# ADC-Z-DOK.net
KiCad netlist of a schematic drawn in Altium Designer
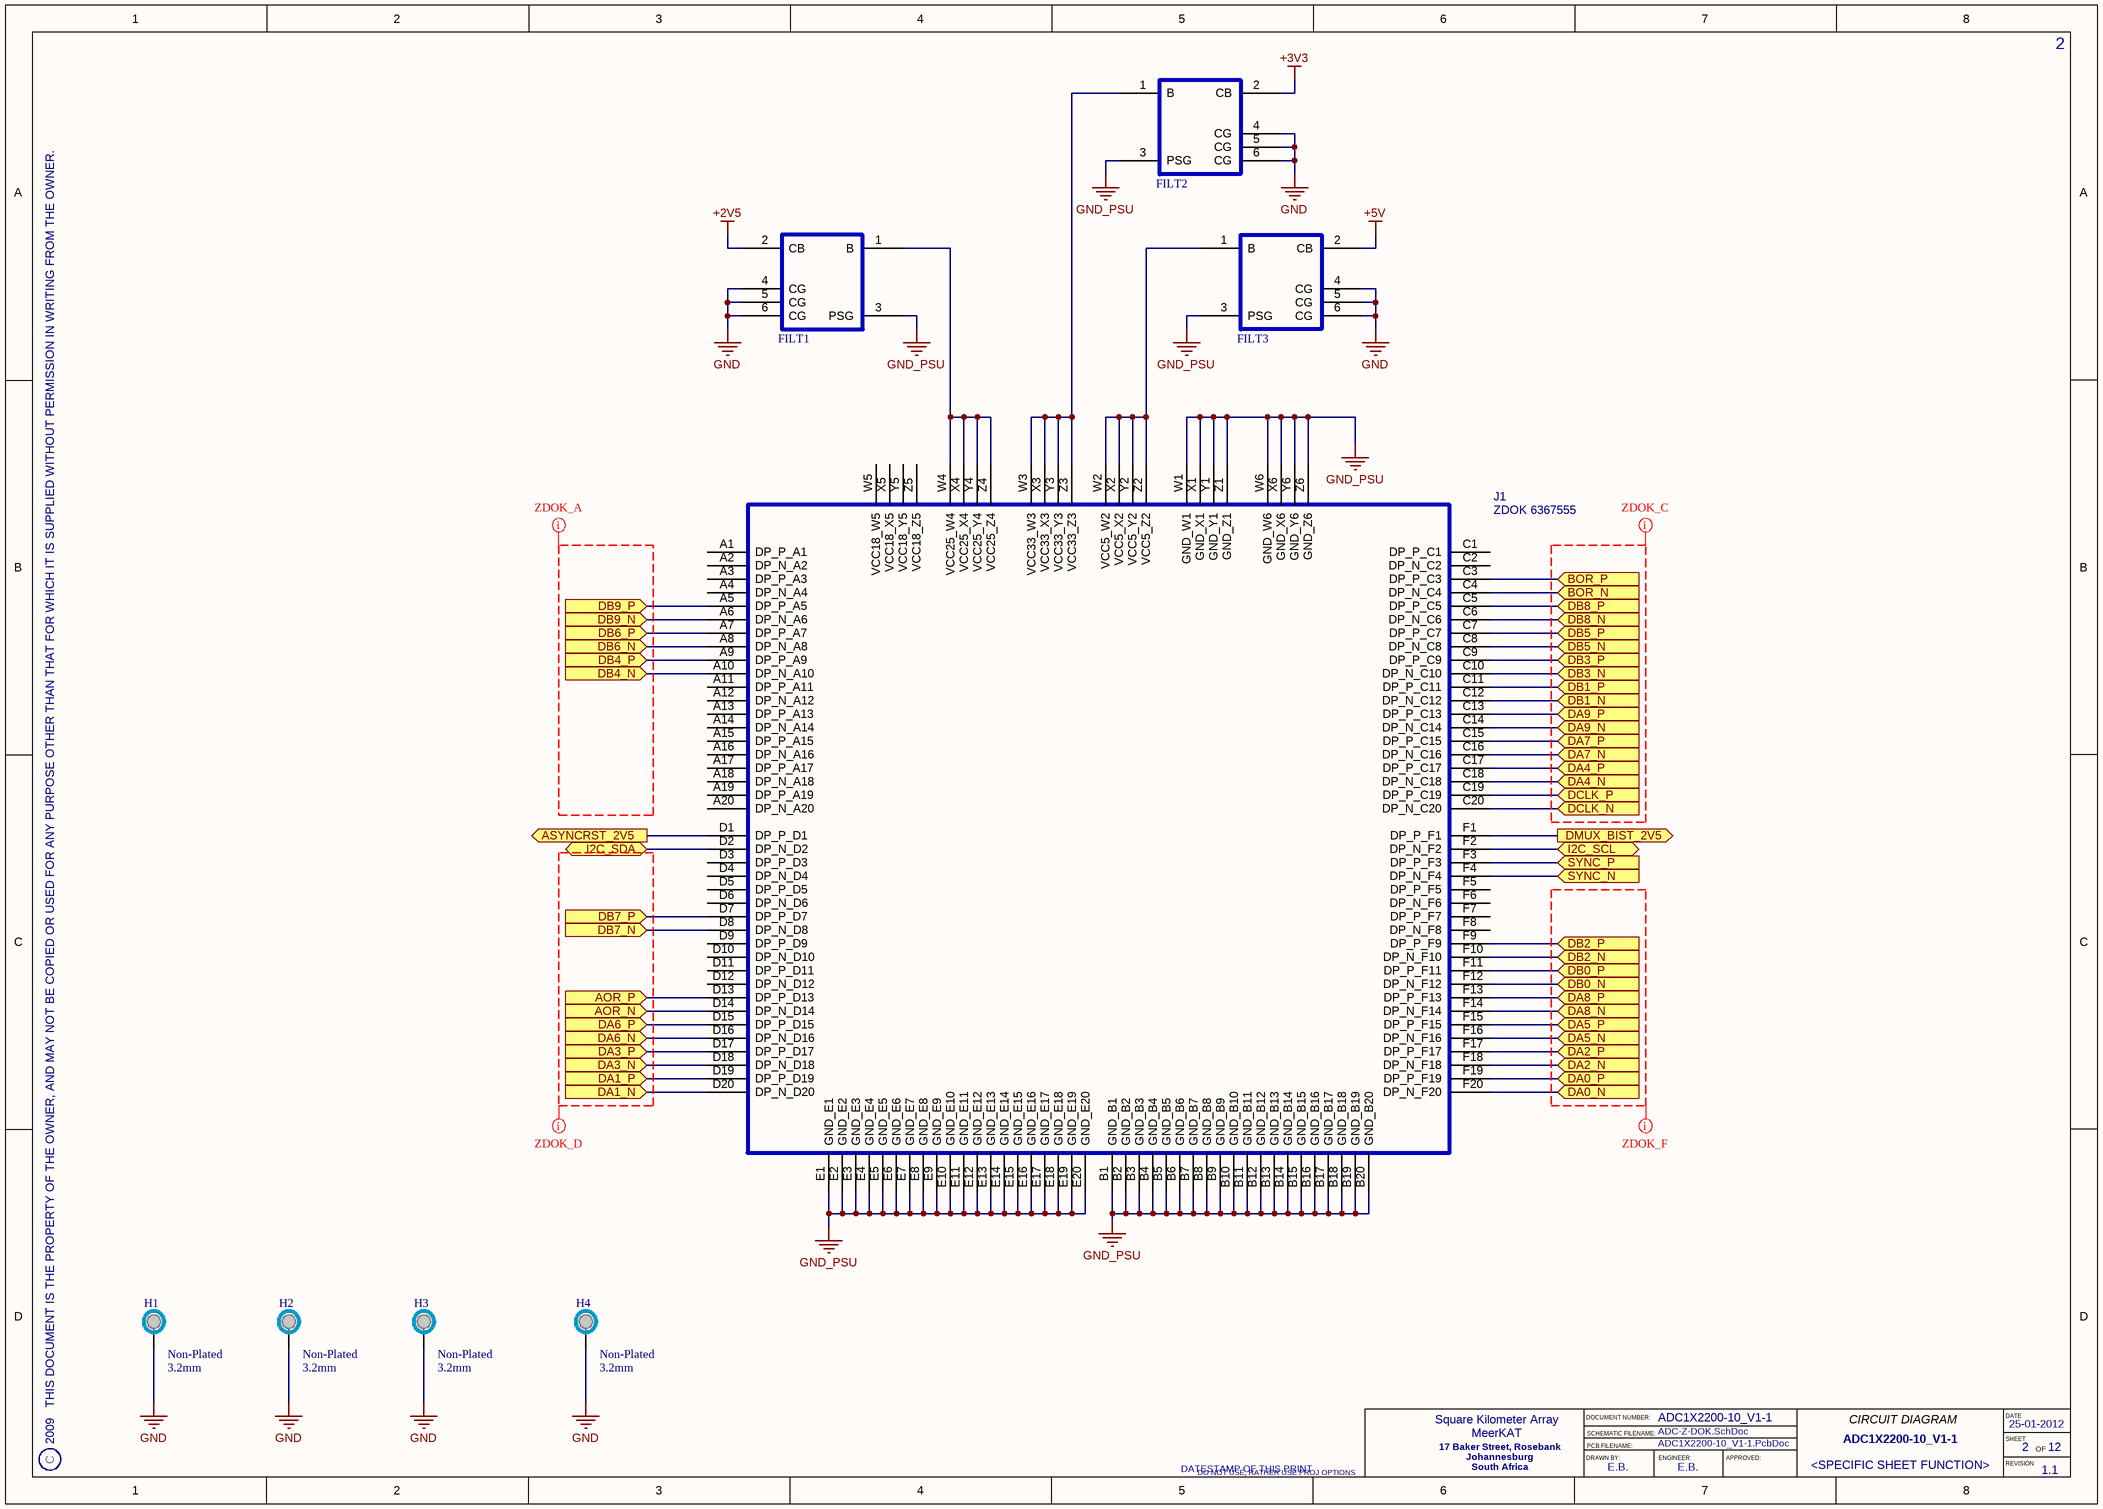
[diagram p0: ADC-Z-DOK.SchDoc]

(export (version "E")
  (design (tool "Eeschema 10.0.6"))
  (components
    (comp (ref "FILT1")
      (value "BNX002-01")
      (footprint "BNX002-01")
      (fields (field (name "CHECKED_BY") "*"))
      (libsource (lib "ADC1X2200-10_V1-0") (part "BNX002-01"))
    )
    (comp (ref "FILT2")
      (value "BNX002-01")
      (footprint "BNX002-01")
      (fields (field (name "CHECKED_BY") "*"))
      (libsource (lib "ADC1X2200-10_V1-0") (part "BNX002-01"))
    )
    (comp (ref "FILT3")
      (value "BNX002-01")
      (footprint "BNX002-01")
      (fields (field (name "CHECKED_BY") "*"))
      (libsource (lib "ADC1X2200-10_V1-0") (part "BNX002-01"))
    )
    (comp (ref "H1")
      (value "Non-Plated")
      (footprint "HOLE")
      (description "PCB Mounting Hole")
      (fields (field (name "HOLEDIA") "3.2mm"))
      (libsource (lib "Analog_Outputs") (part "Unplated Hole_3.2mm"))
    )
    (comp (ref "H2")
      (value "Non-Plated")
      (footprint "HOLE")
      (description "PCB Mounting Hole")
      (fields (field (name "HOLEDIA") "3.2mm"))
      (libsource (lib "Analog_Outputs") (part "Unplated Hole_3.2mm"))
    )
    (comp (ref "H3")
      (value "Non-Plated")
      (footprint "HOLE")
      (description "PCB Mounting Hole")
      (fields (field (name "HOLEDIA") "3.2mm"))
      (libsource (lib "Analog_Outputs") (part "Unplated Hole_3.2mm"))
    )
    (comp (ref "H4")
      (value "Non-Plated")
      (footprint "HOLE")
      (description "PCB Mounting Hole")
      (fields (field (name "HOLEDIA") "3.2mm"))
      (libsource (lib "Analog_Outputs") (part "Unplated Hole_3.2mm"))
    )
    (comp (ref "J1")
      (value "Z-DOK")
      (footprint "TYCO6367555")
      (fields
        (field (name "MANUFACTURER_PN") "ZDOK 6367555")
        (field (name "CREATED_BY") "CT")
        (field (name "CHECKED_BY") "*")
      )
      (libsource (lib "Charles-TEMP") (part "ZDOK 6367555"))
    )
  )
  (nets
    (net (code "1") (name "+2V5") (class "Default")
      (node (ref "FILT1") (pin "2") (pinfunction "CB_2") (pintype "power_in"))
    )
    (net (code "2") (name "+3V3") (class "Default")
      (node (ref "FILT2") (pin "2") (pinfunction "CB_2") (pintype "power_in"))
    )
    (net (code "3") (name "+5V") (class "Default")
      (node (ref "FILT3") (pin "2") (pinfunction "CB_2") (pintype "power_in"))
    )
    (net (code "4") (name "/AOR_N") (class "Default")
      (node (ref "J1") (pin "D14") (pinfunction "DP_N_D14_D14") (pintype "passive"))
    )
    (net (code "5") (name "/AOR_P") (class "Default")
      (node (ref "J1") (pin "D13") (pinfunction "DP_P_D13_D13") (pintype "passive"))
    )
    (net (code "6") (name "/ASYNCRST_2V5") (class "Default")
      (node (ref "J1") (pin "D1") (pinfunction "DP_P_D1_D1") (pintype "passive"))
    )
    (net (code "7") (name "/BOR_N") (class "Default")
      (node (ref "J1") (pin "C4") (pinfunction "DP_N_C4_C4") (pintype "passive"))
    )
    (net (code "8") (name "/BOR_P") (class "Default")
      (node (ref "J1") (pin "C3") (pinfunction "DP_P_C3_C3") (pintype "passive"))
    )
    (net (code "9") (name "/DA0_N") (class "Default")
      (node (ref "J1") (pin "F20") (pinfunction "DP_N_F20_F20") (pintype "passive"))
    )
    (net (code "10") (name "/DA0_P") (class "Default")
      (node (ref "J1") (pin "F19") (pinfunction "DP_P_F19_F19") (pintype "passive"))
    )
    (net (code "11") (name "/DA1_N") (class "Default")
      (node (ref "J1") (pin "D20") (pinfunction "DP_N_D20_D20") (pintype "passive"))
    )
    (net (code "12") (name "/DA1_P") (class "Default")
      (node (ref "J1") (pin "D19") (pinfunction "DP_P_D19_D19") (pintype "passive"))
    )
    (net (code "13") (name "/DA2_N") (class "Default")
      (node (ref "J1") (pin "F18") (pinfunction "DP_N_F18_F18") (pintype "passive"))
    )
    (net (code "14") (name "/DA2_P") (class "Default")
      (node (ref "J1") (pin "F17") (pinfunction "DP_P_F17_F17") (pintype "passive"))
    )
    (net (code "15") (name "/DA3_N") (class "Default")
      (node (ref "J1") (pin "D18") (pinfunction "DP_N_D18_D18") (pintype "passive"))
    )
    (net (code "16") (name "/DA3_P") (class "Default")
      (node (ref "J1") (pin "D17") (pinfunction "DP_P_D17_D17") (pintype "passive"))
    )
    (net (code "17") (name "/DA4_N") (class "Default")
      (node (ref "J1") (pin "C18") (pinfunction "DP_N_C18_C18") (pintype "passive"))
    )
    (net (code "18") (name "/DA4_P") (class "Default")
      (node (ref "J1") (pin "C17") (pinfunction "DP_P_C17_C17") (pintype "passive"))
    )
    (net (code "19") (name "/DA5_N") (class "Default")
      (node (ref "J1") (pin "F16") (pinfunction "DP_N_F16_F16") (pintype "passive"))
    )
    (net (code "20") (name "/DA5_P") (class "Default")
      (node (ref "J1") (pin "F15") (pinfunction "DP_P_F15_F15") (pintype "passive"))
    )
    (net (code "21") (name "/DA6_N") (class "Default")
      (node (ref "J1") (pin "D16") (pinfunction "DP_N_D16_D16") (pintype "passive"))
    )
    (net (code "22") (name "/DA6_P") (class "Default")
      (node (ref "J1") (pin "D15") (pinfunction "DP_P_D15_D15") (pintype "passive"))
    )
    (net (code "23") (name "/DA7_N") (class "Default")
      (node (ref "J1") (pin "C16") (pinfunction "DP_N_C16_C16") (pintype "passive"))
    )
    (net (code "24") (name "/DA7_P") (class "Default")
      (node (ref "J1") (pin "C15") (pinfunction "DP_P_C15_C15") (pintype "passive"))
    )
    (net (code "25") (name "/DA8_N") (class "Default")
      (node (ref "J1") (pin "F14") (pinfunction "DP_N_F14_F14") (pintype "passive"))
    )
    (net (code "26") (name "/DA8_P") (class "Default")
      (node (ref "J1") (pin "F13") (pinfunction "DP_P_F13_F13") (pintype "passive"))
    )
    (net (code "27") (name "/DA9_N") (class "Default")
      (node (ref "J1") (pin "C14") (pinfunction "DP_N_C14_C14") (pintype "passive"))
    )
    (net (code "28") (name "/DA9_P") (class "Default")
      (node (ref "J1") (pin "C13") (pinfunction "DP_P_C13_C13") (pintype "passive"))
    )
    (net (code "29") (name "/DB0_N") (class "Default")
      (node (ref "J1") (pin "F12") (pinfunction "DP_N_F12_F12") (pintype "passive"))
    )
    (net (code "30") (name "/DB0_P") (class "Default")
      (node (ref "J1") (pin "F11") (pinfunction "DP_P_F11_F11") (pintype "passive"))
    )
    (net (code "31") (name "/DB1_N") (class "Default")
      (node (ref "J1") (pin "C12") (pinfunction "DP_N_C12_C12") (pintype "passive"))
    )
    (net (code "32") (name "/DB1_P") (class "Default")
      (node (ref "J1") (pin "C11") (pinfunction "DP_P_C11_C11") (pintype "passive"))
    )
    (net (code "33") (name "/DB2_N") (class "Default")
      (node (ref "J1") (pin "F10") (pinfunction "DP_N_F10_F10") (pintype "passive"))
    )
    (net (code "34") (name "/DB2_P") (class "Default")
      (node (ref "J1") (pin "F9") (pinfunction "DP_P_F9_F9") (pintype "passive"))
    )
    (net (code "35") (name "/DB3_N") (class "Default")
      (node (ref "J1") (pin "C10") (pinfunction "DP_N_C10_C10") (pintype "passive"))
    )
    (net (code "36") (name "/DB3_P") (class "Default")
      (node (ref "J1") (pin "C9") (pinfunction "DP_P_C9_C9") (pintype "passive"))
    )
    (net (code "37") (name "/DB4_N") (class "Default")
      (node (ref "J1") (pin "A10") (pinfunction "DP_N_A10_A10") (pintype "passive"))
    )
    (net (code "38") (name "/DB4_P") (class "Default")
      (node (ref "J1") (pin "A9") (pinfunction "DP_P_A9_A9") (pintype "passive"))
    )
    (net (code "39") (name "/DB5_N") (class "Default")
      (node (ref "J1") (pin "C8") (pinfunction "DP_N_C8_C8") (pintype "passive"))
    )
    (net (code "40") (name "/DB5_P") (class "Default")
      (node (ref "J1") (pin "C7") (pinfunction "DP_P_C7_C7") (pintype "passive"))
    )
    (net (code "41") (name "/DB6_N") (class "Default")
      (node (ref "J1") (pin "A8") (pinfunction "DP_N_A8_A8") (pintype "passive"))
    )
    (net (code "42") (name "/DB6_P") (class "Default")
      (node (ref "J1") (pin "A7") (pinfunction "DP_P_A7_A7") (pintype "passive"))
    )
    (net (code "43") (name "/DB7_N") (class "Default")
      (node (ref "J1") (pin "D8") (pinfunction "DP_N_D8_D8") (pintype "passive"))
    )
    (net (code "44") (name "/DB7_P") (class "Default")
      (node (ref "J1") (pin "D7") (pinfunction "DP_P_D7_D7") (pintype "passive"))
    )
    (net (code "45") (name "/DB8_N") (class "Default")
      (node (ref "J1") (pin "C6") (pinfunction "DP_N_C6_C6") (pintype "passive"))
    )
    (net (code "46") (name "/DB8_P") (class "Default")
      (node (ref "J1") (pin "C5") (pinfunction "DP_P_C5_C5") (pintype "passive"))
    )
    (net (code "47") (name "/DB9_N") (class "Default")
      (node (ref "J1") (pin "A6") (pinfunction "DP_N_A6_A6") (pintype "passive"))
    )
    (net (code "48") (name "/DB9_P") (class "Default")
      (node (ref "J1") (pin "A5") (pinfunction "DP_P_A5_A5") (pintype "passive"))
    )
    (net (code "49") (name "/DCLK_N") (class "Default")
      (node (ref "J1") (pin "C20") (pinfunction "DP_N_C20_C20") (pintype "passive"))
    )
    (net (code "50") (name "/DCLK_P") (class "Default")
      (node (ref "J1") (pin "C19") (pinfunction "DP_P_C19_C19") (pintype "passive"))
    )
    (net (code "51") (name "/DMUX_BIST_2V5") (class "Default")
      (node (ref "J1") (pin "F1") (pinfunction "DP_P_F1_F1") (pintype "passive"))
    )
    (net (code "52") (name "/I2C_SCL") (class "Default")
      (node (ref "J1") (pin "F2") (pinfunction "DP_N_F2_F2") (pintype "passive"))
    )
    (net (code "53") (name "/I2C_SDA") (class "Default")
      (node (ref "J1") (pin "D2") (pinfunction "DP_N_D2_D2") (pintype "passive"))
    )
    (net (code "54") (name "/SYNC_N") (class "Default")
      (node (ref "J1") (pin "F4") (pinfunction "DP_N_F4_F4") (pintype "passive"))
    )
    (net (code "55") (name "/SYNC_P") (class "Default")
      (node (ref "J1") (pin "F3") (pinfunction "DP_P_F3_F3") (pintype "passive"))
    )
    (net (code "56") (name "GND") (class "Default")
      (node (ref "FILT1") (pin "4") (pinfunction "CG_4") (pintype "power_in"))
      (node (ref "FILT1") (pin "5") (pinfunction "CG_5") (pintype "power_in"))
      (node (ref "FILT1") (pin "6") (pinfunction "CG_6") (pintype "power_in"))
      (node (ref "FILT2") (pin "4") (pinfunction "CG_4") (pintype "power_in"))
      (node (ref "FILT2") (pin "5") (pinfunction "CG_5") (pintype "power_in"))
      (node (ref "FILT2") (pin "6") (pinfunction "CG_6") (pintype "power_in"))
      (node (ref "FILT3") (pin "4") (pinfunction "CG_4") (pintype "power_in"))
      (node (ref "FILT3") (pin "5") (pinfunction "CG_5") (pintype "power_in"))
      (node (ref "FILT3") (pin "6") (pinfunction "CG_6") (pintype "power_in"))
      (node (ref "H1") (pin "1") (pinfunction "TP_1") (pintype "passive"))
      (node (ref "H2") (pin "1") (pinfunction "TP_1") (pintype "passive"))
      (node (ref "H3") (pin "1") (pinfunction "TP_1") (pintype "passive"))
      (node (ref "H4") (pin "1") (pinfunction "TP_1") (pintype "passive"))
    )
    (net (code "57") (name "GND_PSU") (class "Default")
      (node (ref "FILT1") (pin "3") (pinfunction "PSG_3") (pintype "power_in"))
      (node (ref "FILT2") (pin "3") (pinfunction "PSG_3") (pintype "power_in"))
      (node (ref "FILT3") (pin "3") (pinfunction "PSG_3") (pintype "power_in"))
      (node (ref "J1") (pin "B1") (pinfunction "GND_B1_B1") (pintype "passive"))
      (node (ref "J1") (pin "B10") (pinfunction "GND_B10_B10") (pintype "passive"))
      (node (ref "J1") (pin "B11") (pinfunction "GND_B11_B11") (pintype "passive"))
      (node (ref "J1") (pin "B12") (pinfunction "GND_B12_B12") (pintype "passive"))
      (node (ref "J1") (pin "B13") (pinfunction "GND_B13_B13") (pintype "passive"))
      (node (ref "J1") (pin "B14") (pinfunction "GND_B14_B14") (pintype "passive"))
      (node (ref "J1") (pin "B15") (pinfunction "GND_B15_B15") (pintype "passive"))
      (node (ref "J1") (pin "B16") (pinfunction "GND_B16_B16") (pintype "passive"))
      (node (ref "J1") (pin "B17") (pinfunction "GND_B17_B17") (pintype "passive"))
      (node (ref "J1") (pin "B18") (pinfunction "GND_B18_B18") (pintype "passive"))
      (node (ref "J1") (pin "B19") (pinfunction "GND_B19_B19") (pintype "passive"))
      (node (ref "J1") (pin "B2") (pinfunction "GND_B2_B2") (pintype "passive"))
      (node (ref "J1") (pin "B20") (pinfunction "GND_B20_B20") (pintype "passive"))
      (node (ref "J1") (pin "B3") (pinfunction "GND_B3_B3") (pintype "passive"))
      (node (ref "J1") (pin "B4") (pinfunction "GND_B4_B4") (pintype "passive"))
      (node (ref "J1") (pin "B5") (pinfunction "GND_B5_B5") (pintype "passive"))
      (node (ref "J1") (pin "B6") (pinfunction "GND_B6_B6") (pintype "passive"))
      (node (ref "J1") (pin "B7") (pinfunction "GND_B7_B7") (pintype "passive"))
      (node (ref "J1") (pin "B8") (pinfunction "GND_B8_B8") (pintype "passive"))
      (node (ref "J1") (pin "B9") (pinfunction "GND_B9_B9") (pintype "passive"))
      (node (ref "J1") (pin "E1") (pinfunction "GND_E1_E1") (pintype "passive"))
      (node (ref "J1") (pin "E10") (pinfunction "GND_E10_E10") (pintype "passive"))
      (node (ref "J1") (pin "E11") (pinfunction "GND_E11_E11") (pintype "passive"))
      (node (ref "J1") (pin "E12") (pinfunction "GND_E12_E12") (pintype "passive"))
      (node (ref "J1") (pin "E13") (pinfunction "GND_E13_E13") (pintype "passive"))
      (node (ref "J1") (pin "E14") (pinfunction "GND_E14_E14") (pintype "passive"))
      (node (ref "J1") (pin "E15") (pinfunction "GND_E15_E15") (pintype "passive"))
      (node (ref "J1") (pin "E16") (pinfunction "GND_E16_E16") (pintype "passive"))
      (node (ref "J1") (pin "E17") (pinfunction "GND_E17_E17") (pintype "passive"))
      (node (ref "J1") (pin "E18") (pinfunction "GND_E18_E18") (pintype "passive"))
      (node (ref "J1") (pin "E19") (pinfunction "GND_E19_E19") (pintype "passive"))
      (node (ref "J1") (pin "E2") (pinfunction "GND_E2_E2") (pintype "passive"))
      (node (ref "J1") (pin "E20") (pinfunction "GND_E20_E20") (pintype "passive"))
      (node (ref "J1") (pin "E3") (pinfunction "GND_E3_E3") (pintype "passive"))
      (node (ref "J1") (pin "E4") (pinfunction "GND_E4_E4") (pintype "passive"))
      (node (ref "J1") (pin "E5") (pinfunction "GND_E5_E5") (pintype "passive"))
      (node (ref "J1") (pin "E6") (pinfunction "GND_E6_E6") (pintype "passive"))
      (node (ref "J1") (pin "E7") (pinfunction "GND_E7_E7") (pintype "passive"))
      (node (ref "J1") (pin "E8") (pinfunction "GND_E8_E8") (pintype "passive"))
      (node (ref "J1") (pin "E9") (pinfunction "GND_E9_E9") (pintype "passive"))
      (node (ref "J1") (pin "W1") (pinfunction "GND_W1_W1") (pintype "passive"))
      (node (ref "J1") (pin "W6") (pinfunction "GND_W6_W6") (pintype "passive"))
      (node (ref "J1") (pin "X1") (pinfunction "GND_X1_X1") (pintype "passive"))
      (node (ref "J1") (pin "X6") (pinfunction "GND_X6_X6") (pintype "passive"))
      (node (ref "J1") (pin "Y1") (pinfunction "GND_Y1_Y1") (pintype "passive"))
      (node (ref "J1") (pin "Y6") (pinfunction "GND_Y6_Y6") (pintype "passive"))
      (node (ref "J1") (pin "Z1") (pinfunction "GND_Z1_Z1") (pintype "passive"))
      (node (ref "J1") (pin "Z6") (pinfunction "GND_Z6_Z6") (pintype "passive"))
    )
    (net (code "58") (name "Net-(FILT1-B)") (class "Default")
      (node (ref "FILT1") (pin "1") (pinfunction "B_1") (pintype "power_in"))
      (node (ref "J1") (pin "W4") (pinfunction "VCC25_W4_W4") (pintype "power_in"))
      (node (ref "J1") (pin "X4") (pinfunction "VCC25_X4_X4") (pintype "power_in"))
      (node (ref "J1") (pin "Y4") (pinfunction "VCC25_Y4_Y4") (pintype "power_in"))
      (node (ref "J1") (pin "Z4") (pinfunction "VCC25_Z4_Z4") (pintype "power_in"))
    )
    (net (code "59") (name "Net-(FILT2-B)") (class "Default")
      (node (ref "FILT2") (pin "1") (pinfunction "B_1") (pintype "power_in"))
      (node (ref "J1") (pin "W3") (pinfunction "VCC33_W3_W3") (pintype "power_in"))
      (node (ref "J1") (pin "X3") (pinfunction "VCC33_X3_X3") (pintype "power_in"))
      (node (ref "J1") (pin "Y3") (pinfunction "VCC33_Y3_Y3") (pintype "power_in"))
      (node (ref "J1") (pin "Z3") (pinfunction "VCC33_Z3_Z3") (pintype "power_in"))
    )
    (net (code "60") (name "Net-(FILT3-B)") (class "Default")
      (node (ref "FILT3") (pin "1") (pinfunction "B_1") (pintype "power_in"))
      (node (ref "J1") (pin "W2") (pinfunction "VCC5_W2_W2") (pintype "power_in"))
      (node (ref "J1") (pin "X2") (pinfunction "VCC5_X2_X2") (pintype "power_in"))
      (node (ref "J1") (pin "Y2") (pinfunction "VCC5_Y2_Y2") (pintype "power_in"))
      (node (ref "J1") (pin "Z2") (pinfunction "VCC5_Z2_Z2") (pintype "power_in"))
    )
    (net (code "61") (name "unconnected-(J1-DP_N_A2-PadA2)") (class "Default")
      (node (ref "J1") (pin "A2") (pinfunction "DP_N_A2_A2") (pintype "passive"))
    )
    (net (code "62") (name "unconnected-(J1-DP_N_A4-PadA4)") (class "Default")
      (node (ref "J1") (pin "A4") (pinfunction "DP_N_A4_A4") (pintype "passive"))
    )
    (net (code "63") (name "unconnected-(J1-DP_N_A12-PadA12)") (class "Default")
      (node (ref "J1") (pin "A12") (pinfunction "DP_N_A12_A12") (pintype "passive"))
    )
    (net (code "64") (name "unconnected-(J1-DP_N_A14-PadA14)") (class "Default")
      (node (ref "J1") (pin "A14") (pinfunction "DP_N_A14_A14") (pintype "passive"))
    )
    (net (code "65") (name "unconnected-(J1-DP_N_A16-PadA16)") (class "Default")
      (node (ref "J1") (pin "A16") (pinfunction "DP_N_A16_A16") (pintype "passive"))
    )
    (net (code "66") (name "unconnected-(J1-DP_N_A18-PadA18)") (class "Default")
      (node (ref "J1") (pin "A18") (pinfunction "DP_N_A18_A18") (pintype "passive"))
    )
    (net (code "67") (name "unconnected-(J1-DP_N_A20-PadA20)") (class "Default")
      (node (ref "J1") (pin "A20") (pinfunction "DP_N_A20_A20") (pintype "passive"))
    )
    (net (code "68") (name "unconnected-(J1-DP_N_C2-PadC2)") (class "Default")
      (node (ref "J1") (pin "C2") (pinfunction "DP_N_C2_C2") (pintype "passive"))
    )
    (net (code "69") (name "unconnected-(J1-DP_N_D4-PadD4)") (class "Default")
      (node (ref "J1") (pin "D4") (pinfunction "DP_N_D4_D4") (pintype "passive"))
    )
    (net (code "70") (name "unconnected-(J1-DP_N_D6-PadD6)") (class "Default")
      (node (ref "J1") (pin "D6") (pinfunction "DP_N_D6_D6") (pintype "passive"))
    )
    (net (code "71") (name "unconnected-(J1-DP_N_D10-PadD10)") (class "Default")
      (node (ref "J1") (pin "D10") (pinfunction "DP_N_D10_D10") (pintype "passive"))
    )
    (net (code "72") (name "unconnected-(J1-DP_N_D12-PadD12)") (class "Default")
      (node (ref "J1") (pin "D12") (pinfunction "DP_N_D12_D12") (pintype "passive"))
    )
    (net (code "73") (name "unconnected-(J1-DP_N_F6-PadF6)") (class "Default")
      (node (ref "J1") (pin "F6") (pinfunction "DP_N_F6_F6") (pintype "passive"))
    )
    (net (code "74") (name "unconnected-(J1-DP_N_F8-PadF8)") (class "Default")
      (node (ref "J1") (pin "F8") (pinfunction "DP_N_F8_F8") (pintype "passive"))
    )
    (net (code "75") (name "unconnected-(J1-DP_P_A1-PadA1)") (class "Default")
      (node (ref "J1") (pin "A1") (pinfunction "DP_P_A1_A1") (pintype "passive"))
    )
    (net (code "76") (name "unconnected-(J1-DP_P_A3-PadA3)") (class "Default")
      (node (ref "J1") (pin "A3") (pinfunction "DP_P_A3_A3") (pintype "passive"))
    )
    (net (code "77") (name "unconnected-(J1-DP_P_A11-PadA11)") (class "Default")
      (node (ref "J1") (pin "A11") (pinfunction "DP_P_A11_A11") (pintype "passive"))
    )
    (net (code "78") (name "unconnected-(J1-DP_P_A13-PadA13)") (class "Default")
      (node (ref "J1") (pin "A13") (pinfunction "DP_P_A13_A13") (pintype "passive"))
    )
    (net (code "79") (name "unconnected-(J1-DP_P_A15-PadA15)") (class "Default")
      (node (ref "J1") (pin "A15") (pinfunction "DP_P_A15_A15") (pintype "passive"))
    )
    (net (code "80") (name "unconnected-(J1-DP_P_A17-PadA17)") (class "Default")
      (node (ref "J1") (pin "A17") (pinfunction "DP_P_A17_A17") (pintype "passive"))
    )
    (net (code "81") (name "unconnected-(J1-DP_P_A19-PadA19)") (class "Default")
      (node (ref "J1") (pin "A19") (pinfunction "DP_P_A19_A19") (pintype "passive"))
    )
    (net (code "82") (name "unconnected-(J1-DP_P_C1-PadC1)") (class "Default")
      (node (ref "J1") (pin "C1") (pinfunction "DP_P_C1_C1") (pintype "passive"))
    )
    (net (code "83") (name "unconnected-(J1-DP_P_D3-PadD3)") (class "Default")
      (node (ref "J1") (pin "D3") (pinfunction "DP_P_D3_D3") (pintype "passive"))
    )
    (net (code "84") (name "unconnected-(J1-DP_P_D5-PadD5)") (class "Default")
      (node (ref "J1") (pin "D5") (pinfunction "DP_P_D5_D5") (pintype "passive"))
    )
    (net (code "85") (name "unconnected-(J1-DP_P_D9-PadD9)") (class "Default")
      (node (ref "J1") (pin "D9") (pinfunction "DP_P_D9_D9") (pintype "passive"))
    )
    (net (code "86") (name "unconnected-(J1-DP_P_D11-PadD11)") (class "Default")
      (node (ref "J1") (pin "D11") (pinfunction "DP_P_D11_D11") (pintype "passive"))
    )
    (net (code "87") (name "unconnected-(J1-DP_P_F5-PadF5)") (class "Default")
      (node (ref "J1") (pin "F5") (pinfunction "DP_P_F5_F5") (pintype "passive"))
    )
    (net (code "88") (name "unconnected-(J1-DP_P_F7-PadF7)") (class "Default")
      (node (ref "J1") (pin "F7") (pinfunction "DP_P_F7_F7") (pintype "passive"))
    )
    (net (code "89") (name "unconnected-(J1-VCC18_W5-PadW5)") (class "Default")
      (node (ref "J1") (pin "W5") (pinfunction "VCC18_W5_W5") (pintype "power_in"))
    )
    (net (code "90") (name "unconnected-(J1-VCC18_X5-PadX5)") (class "Default")
      (node (ref "J1") (pin "X5") (pinfunction "VCC18_X5_X5") (pintype "power_in"))
    )
    (net (code "91") (name "unconnected-(J1-VCC18_Y5-PadY5)") (class "Default")
      (node (ref "J1") (pin "Y5") (pinfunction "VCC18_Y5_Y5") (pintype "power_in"))
    )
    (net (code "92") (name "unconnected-(J1-VCC18_Z5-PadZ5)") (class "Default")
      (node (ref "J1") (pin "Z5") (pinfunction "VCC18_Z5_Z5") (pintype "power_in"))
    )
  )
)
